# guhPLC_SmartMeterInterface.net
KiCad netlist of a schematic drawn in EAGLE
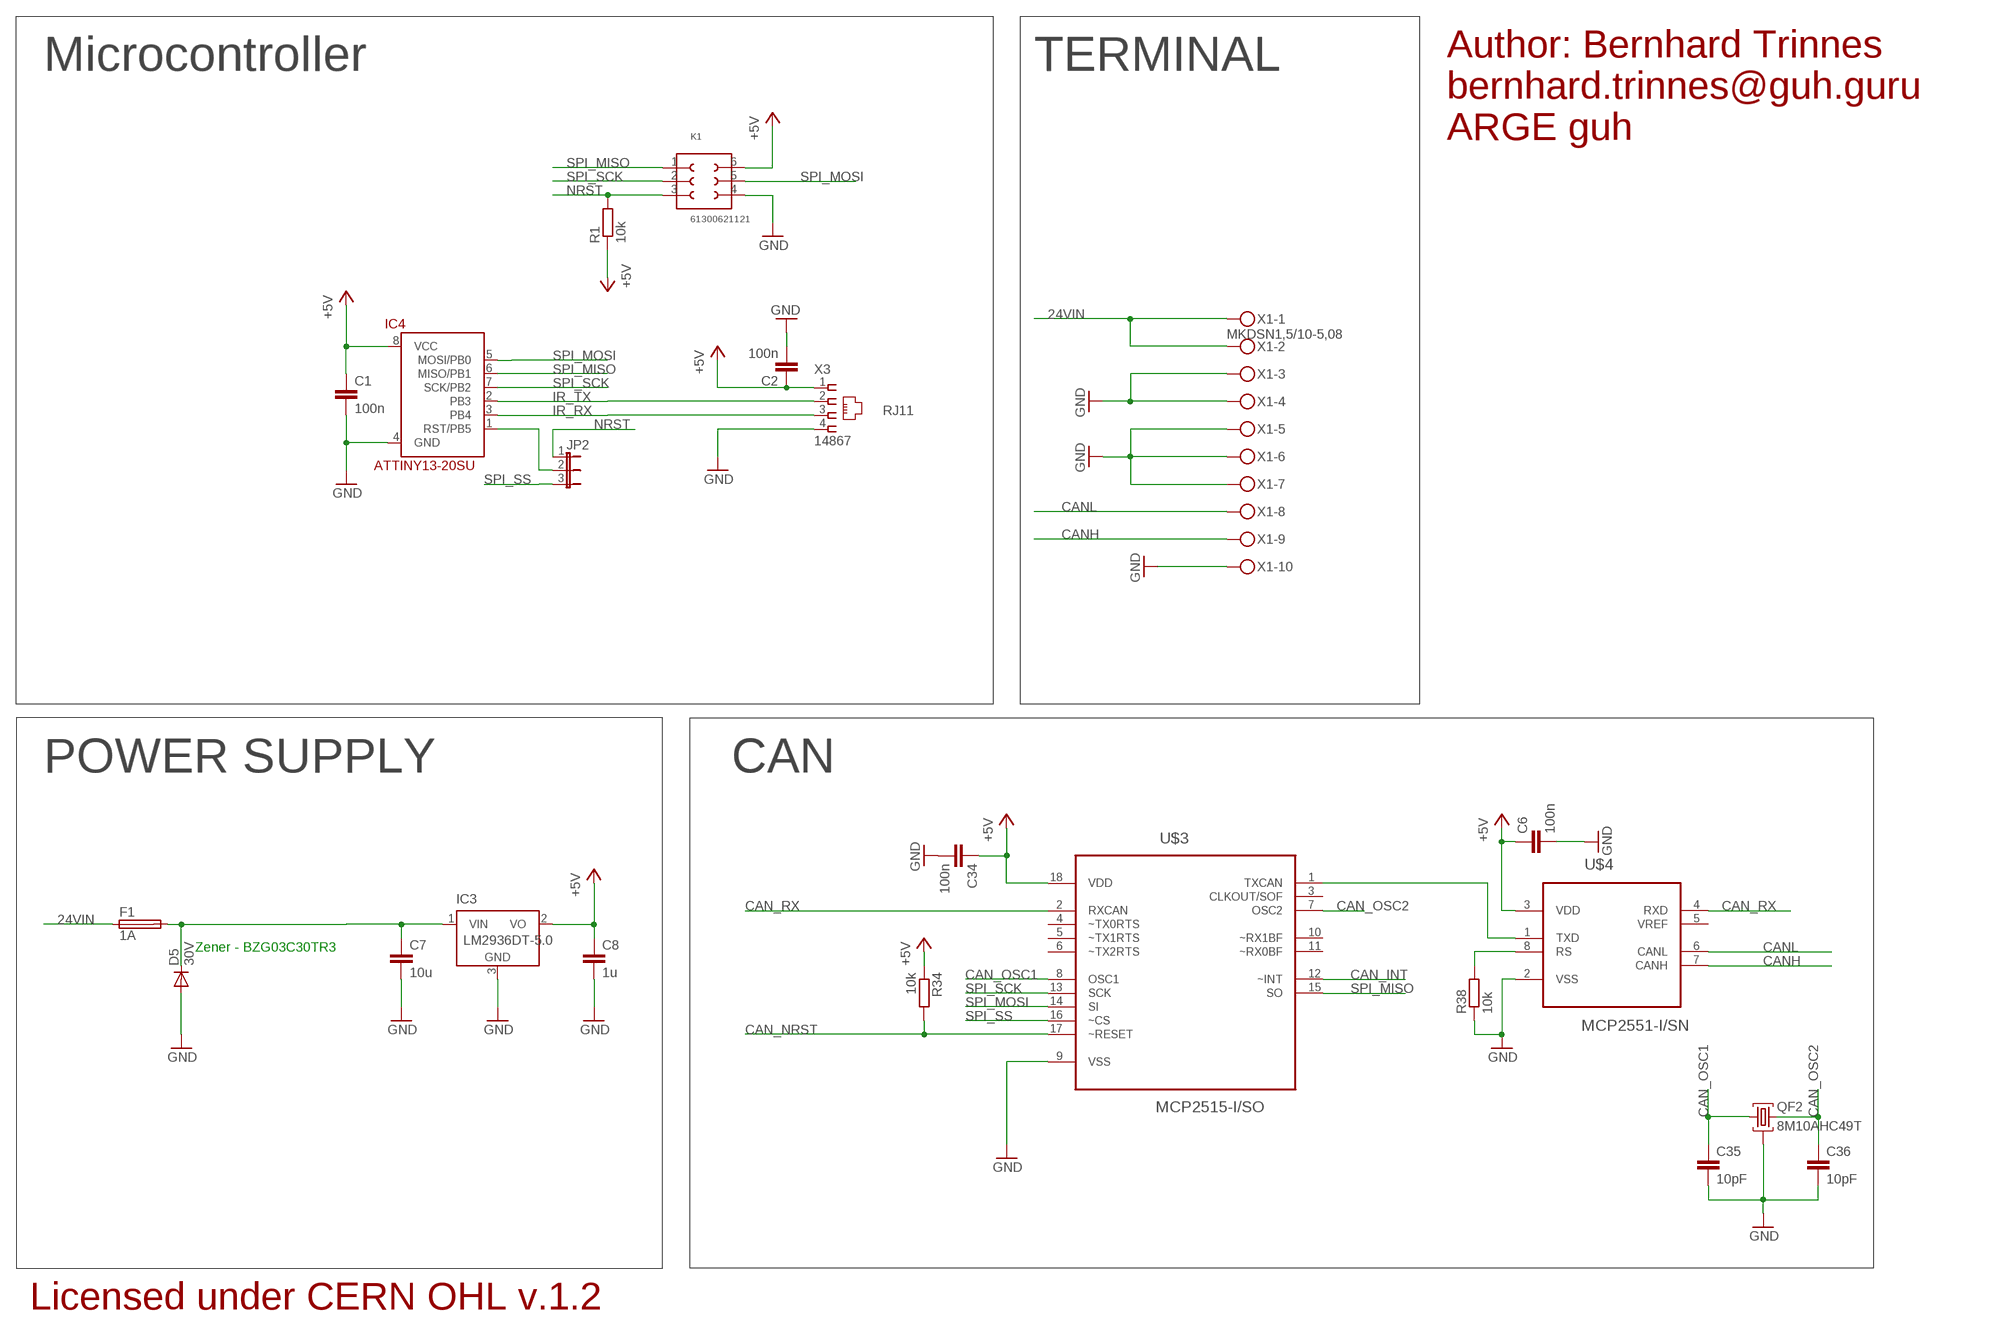
[diagram p0: schematic, sheet 1]

(export (version "E")
  (design (tool "Eeschema 10.0.6"))
  (components
    (comp (ref "C1")
      (value "100n")
      (footprint "eagle-import:C0603")
      (libsource (lib "eagle-import") (part "C-EUC0603"))
    )
    (comp (ref "C2")
      (value "100n")
      (footprint "eagle-import:C0603")
      (libsource (lib "eagle-import") (part "C-EUC0603"))
    )
    (comp (ref "C6")
      (value "100n")
      (footprint "eagle-import:C0603")
      (libsource (lib "eagle-import") (part "C-EUC0603"))
    )
    (comp (ref "C7")
      (value "10u")
      (footprint "eagle-import:C1206")
      (libsource (lib "eagle-import") (part "C-EUC1206"))
    )
    (comp (ref "C8")
      (value "1u")
      (footprint "eagle-import:C0603")
      (libsource (lib "eagle-import") (part "C-EUC0603"))
    )
    (comp (ref "C34")
      (value "100n")
      (footprint "eagle-import:C0603")
      (libsource (lib "eagle-import") (part "C-EUC0603"))
    )
    (comp (ref "C35")
      (value "10pF")
      (footprint "eagle-import:C0603")
      (libsource (lib "eagle-import") (part "C-EUC0603"))
    )
    (comp (ref "C36")
      (value "10pF")
      (footprint "eagle-import:C0603")
      (libsource (lib "eagle-import") (part "C-EUC0603"))
    )
    (comp (ref "D5")
      (value "30V")
      (footprint "eagle-import:DO214AC")
      (libsource (lib "eagle-import") (part "DIODE-DO214AC"))
    )
    (comp (ref "F1")
      (value "1A")
      (footprint "eagle-import:LITTLEFUSE")
      (libsource (lib "eagle-import") (part "LITTLEFUSE"))
    )
    (comp (ref "IC3")
      (value "LM2936DT-5.0")
      (footprint "eagle-import:TO252")
      (fields (field (name "MF") "NATIONAL SEMICONDUCTOR") (field (name "MPN") "LM2936DT-5.0/NOPB"))
      (libsource (lib "eagle-import") (part "LM2936?DT-5.0"))
    )
    (comp (ref "IC4")
      (value "ATTINY13-20SU")
      (footprint "eagle-import:SOIC8")
      (libsource (lib "eagle-import") (part "ATTINY13-20SU"))
    )
    (comp (ref "JP2")
      (value "JP2E")
      (footprint "eagle-import:JP2")
      (libsource (lib "eagle-import") (part "JP2E"))
    )
    (comp (ref "K1")
      (value "61300621121")
      (footprint "eagle-import:61300621121")
      (libsource (lib "eagle-import") (part "61300621121"))
    )
    (comp (ref "QF2")
      (value "8M10AHC49T")
      (footprint "eagle-import:HC49U")
      (fields (field (name "OC_FARNELL") "unknown") (field (name "OC_NEWARK") "unknown"))
      (libsource (lib "eagle-import") (part "8M10AHC49T"))
    )
    (comp (ref "R1")
      (value "10k")
      (footprint "eagle-import:R0603")
      (libsource (lib "eagle-import") (part "R-EU_R0603"))
    )
    (comp (ref "R34")
      (value "10k")
      (footprint "eagle-import:R0603")
      (libsource (lib "eagle-import") (part "R-EU_R0603"))
    )
    (comp (ref "R38")
      (value "10k")
      (footprint "eagle-import:R0603")
      (libsource (lib "eagle-import") (part "R-EU_R0603"))
    )
    (comp (ref "U$3")
      (value "MCP2515-I/SO")
      (footprint "eagle-import:SOIC127P1034X264-18N")
      (libsource (lib "eagle-import") (part "MCP2515-I/SO"))
    )
    (comp (ref "U$4")
      (value "MCP2551-I/SN")
      (footprint "eagle-import:SOIC127P600X175-8N")
      (libsource (lib "eagle-import") (part "MCP2551-I/SN"))
    )
    (comp (ref "X1")
      (value "MKDSN1,5/10-5,08")
      (footprint "eagle-import:MKDSN1,5_10-5,08")
      (fields (field (name "MPN") "SMKDSN1,5/10-5,08"))
      (libsource (lib "eagle-import") (part "MKDSN1,5/10-5,08"))
    )
    (comp (ref "X3")
      (value "14867")
      (footprint "eagle-import:14867")
      (libsource (lib "eagle-import") (part "14867"))
    )
  )
  (nets
    (net (code "1") (name "+5V") (class "Default")
      (node (ref "C1") (pin "1") (pinfunction "1_1") (pintype "passive"))
      (node (ref "C2") (pin "1") (pinfunction "1_1") (pintype "passive"))
      (node (ref "C34") (pin "1") (pinfunction "1_1") (pintype "passive"))
      (node (ref "C6") (pin "1") (pinfunction "1_1") (pintype "passive"))
      (node (ref "C8") (pin "1") (pinfunction "1_1") (pintype "passive"))
      (node (ref "IC3") (pin "2") (pinfunction "VO_2") (pintype "passive"))
      (node (ref "IC4") (pin "8") (pinfunction "VCC_8") (pintype "power_in"))
      (node (ref "K1") (pin "6") (pinfunction "6_6") (pintype "passive"))
      (node (ref "R1") (pin "1") (pinfunction "1_1") (pintype "passive"))
      (node (ref "R34") (pin "1") (pinfunction "1_1") (pintype "passive"))
      (node (ref "U$3") (pin "18") (pinfunction "VDD_18") (pintype "power_in"))
      (node (ref "U$4") (pin "3") (pinfunction "VDD_3") (pintype "power_in"))
      (node (ref "X3") (pin "1") (pinfunction "1_1") (pintype "passive"))
    )
    (net (code "2") (name "/24VIN") (class "Default")
      (node (ref "F1") (pin "1") (pinfunction "1_1") (pintype "passive"))
      (node (ref "X1") (pin "1") (pinfunction "KL_1") (pintype "passive"))
      (node (ref "X1") (pin "2") (pinfunction "KL_2") (pintype "passive"))
    )
    (net (code "3") (name "/CANH") (class "Default")
      (node (ref "U$4") (pin "7") (pinfunction "CANH_7") (pintype "bidirectional"))
      (node (ref "X1") (pin "9") (pinfunction "KL_9") (pintype "passive"))
    )
    (net (code "4") (name "/CANL") (class "Default")
      (node (ref "U$4") (pin "6") (pinfunction "CANL_6") (pintype "bidirectional"))
      (node (ref "X1") (pin "8") (pinfunction "KL_8") (pintype "passive"))
    )
    (net (code "5") (name "/CAN_INT") (class "Default")
      (node (ref "U$3") (pin "12") (pinfunction "~{INT}_12") (pintype "output"))
    )
    (net (code "6") (name "/CAN_NRST") (class "Default")
      (node (ref "R34") (pin "2") (pinfunction "2_2") (pintype "passive"))
      (node (ref "U$3") (pin "17") (pinfunction "~{RESET}_17") (pintype "input"))
    )
    (net (code "7") (name "/CAN_OSC1") (class "Default")
      (node (ref "C35") (pin "1") (pinfunction "1_1") (pintype "passive"))
      (node (ref "QF2") (pin "1") (pinfunction "1_1") (pintype "passive"))
      (node (ref "U$3") (pin "8") (pinfunction "OSC1_8") (pintype "input"))
    )
    (net (code "8") (name "/CAN_OSC2") (class "Default")
      (node (ref "C36") (pin "1") (pinfunction "1_1") (pintype "passive"))
      (node (ref "QF2") (pin "3") (pinfunction "3_3") (pintype "passive"))
      (node (ref "U$3") (pin "7") (pinfunction "OSC2_7") (pintype "output"))
    )
    (net (code "9") (name "/CAN_RX") (class "Default")
      (node (ref "U$3") (pin "2") (pinfunction "RXCAN_2") (pintype "input"))
      (node (ref "U$4") (pin "4") (pinfunction "RXD_4") (pintype "output"))
    )
    (net (code "10") (name "/IR_RX") (class "Default")
      (node (ref "IC4") (pin "3") (pinfunction "PB4_3") (pintype "bidirectional"))
      (node (ref "X3") (pin "3") (pinfunction "3_3") (pintype "passive"))
    )
    (net (code "11") (name "/IR_TX") (class "Default")
      (node (ref "IC4") (pin "2") (pinfunction "PB3_2") (pintype "bidirectional"))
      (node (ref "X3") (pin "2") (pinfunction "2_2") (pintype "passive"))
    )
    (net (code "12") (name "/NRST") (class "Default")
      (node (ref "JP2") (pin "1") (pinfunction "1_1") (pintype "passive"))
      (node (ref "K1") (pin "3") (pinfunction "3_3") (pintype "passive"))
      (node (ref "R1") (pin "2") (pinfunction "2_2") (pintype "passive"))
    )
    (net (code "13") (name "/SPI_MISO") (class "Default")
      (node (ref "IC4") (pin "6") (pinfunction "MISO/PB1_6") (pintype "bidirectional"))
      (node (ref "K1") (pin "1") (pinfunction "1_1") (pintype "passive"))
      (node (ref "U$3") (pin "15") (pinfunction "SO_15") (pintype "output"))
    )
    (net (code "14") (name "/SPI_MOSI") (class "Default")
      (node (ref "IC4") (pin "5") (pinfunction "MOSI/PB0_5") (pintype "bidirectional"))
      (node (ref "K1") (pin "5") (pinfunction "5_5") (pintype "passive"))
      (node (ref "U$3") (pin "14") (pinfunction "SI_14") (pintype "input"))
    )
    (net (code "15") (name "/SPI_SCK") (class "Default")
      (node (ref "IC4") (pin "7") (pinfunction "SCK/PB2_7") (pintype "bidirectional"))
      (node (ref "K1") (pin "2") (pinfunction "2_2") (pintype "passive"))
      (node (ref "U$3") (pin "13") (pinfunction "SCK_13") (pintype "input"))
    )
    (net (code "16") (name "/SPI_SS") (class "Default")
      (node (ref "JP2") (pin "3") (pinfunction "3_3") (pintype "passive"))
      (node (ref "U$3") (pin "16") (pinfunction "~{CS}_16") (pintype "input"))
    )
    (net (code "17") (name "GND") (class "Default")
      (node (ref "C1") (pin "2") (pinfunction "2_2") (pintype "passive"))
      (node (ref "C2") (pin "2") (pinfunction "2_2") (pintype "passive"))
      (node (ref "C34") (pin "2") (pinfunction "2_2") (pintype "passive"))
      (node (ref "C35") (pin "2") (pinfunction "2_2") (pintype "passive"))
      (node (ref "C36") (pin "2") (pinfunction "2_2") (pintype "passive"))
      (node (ref "C6") (pin "2") (pinfunction "2_2") (pintype "passive"))
      (node (ref "C7") (pin "2") (pinfunction "2_2") (pintype "passive"))
      (node (ref "C8") (pin "2") (pinfunction "2_2") (pintype "passive"))
      (node (ref "D5") (pin "A") (pinfunction "A_A") (pintype "passive"))
      (node (ref "IC3") (pin "3") (pinfunction "GND_3") (pintype "passive"))
      (node (ref "IC4") (pin "4") (pinfunction "GND_4") (pintype "power_in"))
      (node (ref "K1") (pin "4") (pinfunction "4_4") (pintype "passive"))
      (node (ref "QF2") (pin "2") (pinfunction "2_2") (pintype "passive"))
      (node (ref "R38") (pin "1") (pinfunction "1_1") (pintype "passive"))
      (node (ref "U$3") (pin "9") (pinfunction "VSS_9") (pintype "power_in"))
      (node (ref "U$4") (pin "2") (pinfunction "VSS_2") (pintype "passive"))
      (node (ref "X1") (pin "10") (pinfunction "KL_10") (pintype "passive"))
      (node (ref "X1") (pin "3") (pinfunction "KL_3") (pintype "passive"))
      (node (ref "X1") (pin "4") (pinfunction "KL_4") (pintype "passive"))
      (node (ref "X1") (pin "5") (pinfunction "KL_5") (pintype "passive"))
      (node (ref "X1") (pin "6") (pinfunction "KL_6") (pintype "passive"))
      (node (ref "X1") (pin "7") (pinfunction "KL_7") (pintype "passive"))
      (node (ref "X3") (pin "4") (pinfunction "4_4") (pintype "passive"))
    )
    (net (code "18") (name "Net-(IC3-VIN)") (class "Default")
      (node (ref "C7") (pin "1") (pinfunction "1_1") (pintype "passive"))
      (node (ref "D5") (pin "C") (pinfunction "C_C") (pintype "passive"))
      (node (ref "F1") (pin "2") (pinfunction "2_2") (pintype "passive"))
      (node (ref "IC3") (pin "1") (pinfunction "VIN_1") (pintype "input"))
    )
    (net (code "19") (name "Net-(IC4-RST{slash}PB5)") (class "Default")
      (node (ref "IC4") (pin "1") (pinfunction "RST/PB5_1") (pintype "bidirectional"))
      (node (ref "JP2") (pin "2") (pinfunction "2_2") (pintype "passive"))
    )
    (net (code "20") (name "Net-(U$3-TXCAN)") (class "Default")
      (node (ref "U$3") (pin "1") (pinfunction "TXCAN_1") (pintype "output"))
      (node (ref "U$4") (pin "1") (pinfunction "TXD_1") (pintype "input"))
    )
    (net (code "21") (name "Net-(U$4-RS)") (class "Default")
      (node (ref "R38") (pin "2") (pinfunction "2_2") (pintype "passive"))
      (node (ref "U$4") (pin "8") (pinfunction "RS_8") (pintype "input"))
    )
    (net (code "22") (name "unconnected-(U$3-CLKOUT{slash}SOF-Pad3)") (class "Default")
      (node (ref "U$3") (pin "3") (pinfunction "CLKOUT/SOF_3") (pintype "output"))
    )
    (net (code "23") (name "unconnected-(U$3-~{RX0BF}-Pad11)") (class "Default")
      (node (ref "U$3") (pin "11") (pinfunction "~{RX0BF}_11") (pintype "output"))
    )
    (net (code "24") (name "unconnected-(U$3-~{RX1BF}-Pad10)") (class "Default")
      (node (ref "U$3") (pin "10") (pinfunction "~{RX1BF}_10") (pintype "output"))
    )
    (net (code "25") (name "unconnected-(U$3-~{TX0RTS}-Pad4)") (class "Default")
      (node (ref "U$3") (pin "4") (pinfunction "~{TX0RTS}_4") (pintype "input"))
    )
    (net (code "26") (name "unconnected-(U$3-~{TX1RTS}-Pad5)") (class "Default")
      (node (ref "U$3") (pin "5") (pinfunction "~{TX1RTS}_5") (pintype "input"))
    )
    (net (code "27") (name "unconnected-(U$3-~{TX2RTS}-Pad6)") (class "Default")
      (node (ref "U$3") (pin "6") (pinfunction "~{TX2RTS}_6") (pintype "input"))
    )
    (net (code "28") (name "unconnected-(U$4-VREF-Pad5)") (class "Default")
      (node (ref "U$4") (pin "5") (pinfunction "VREF_5") (pintype "output"))
    )
  )
)
